# iov-board-1_2.net
KiCad netlist of a schematic drawn in EAGLE
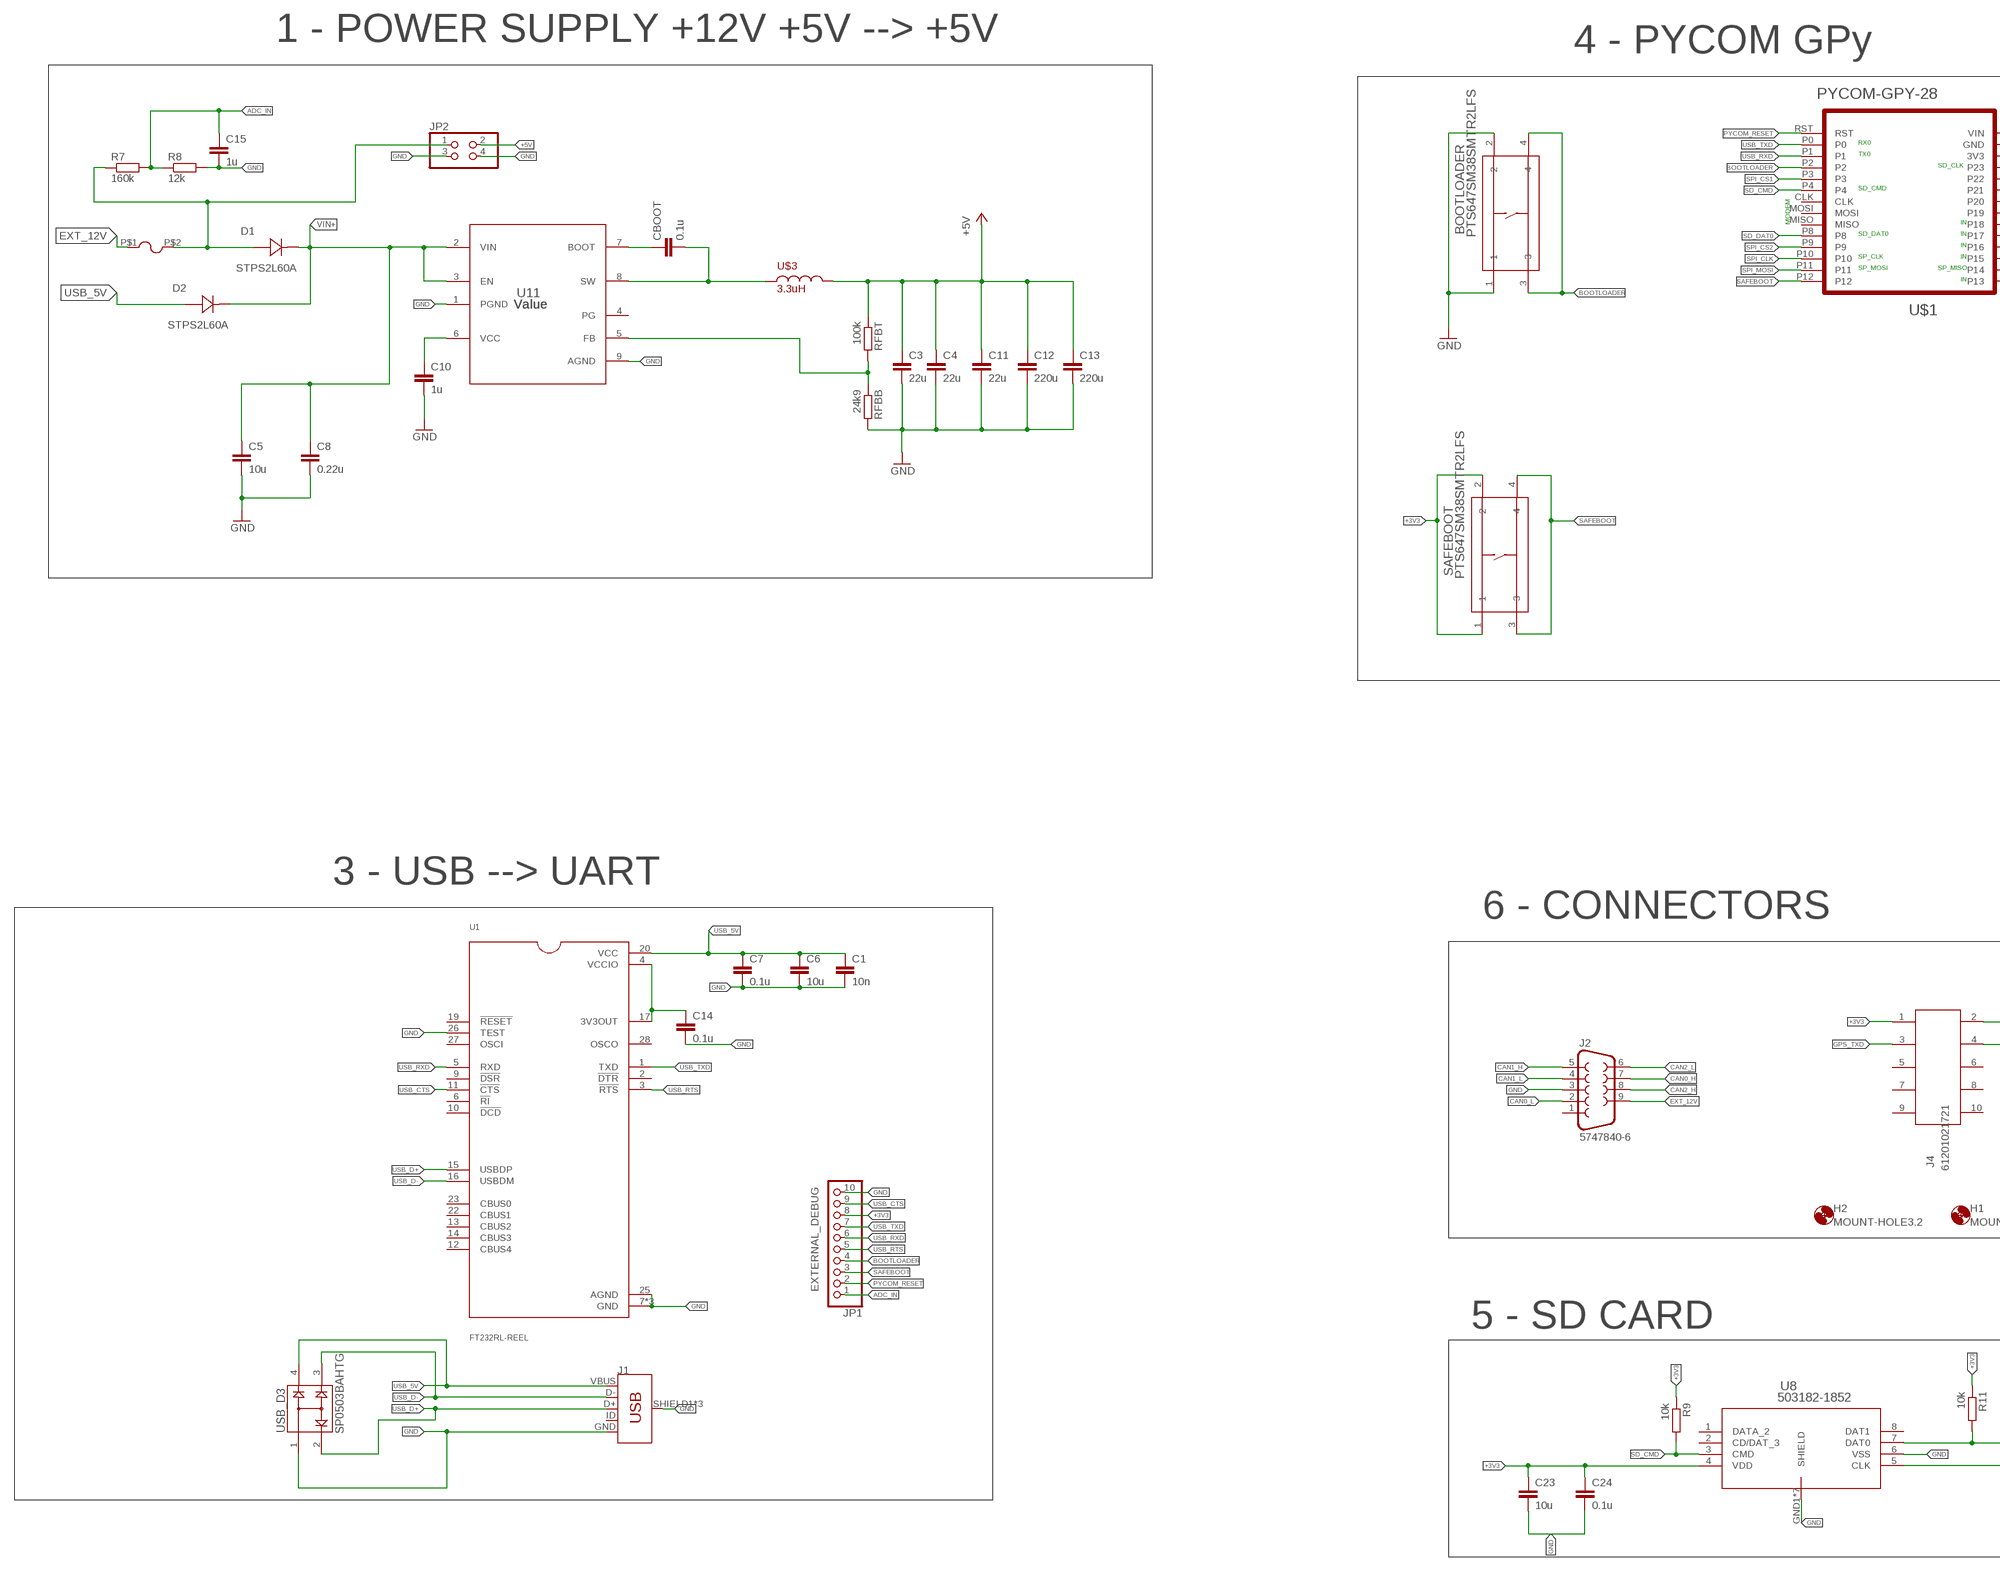
[diagram p0: schematic, sheet 1, part 1 of 2]
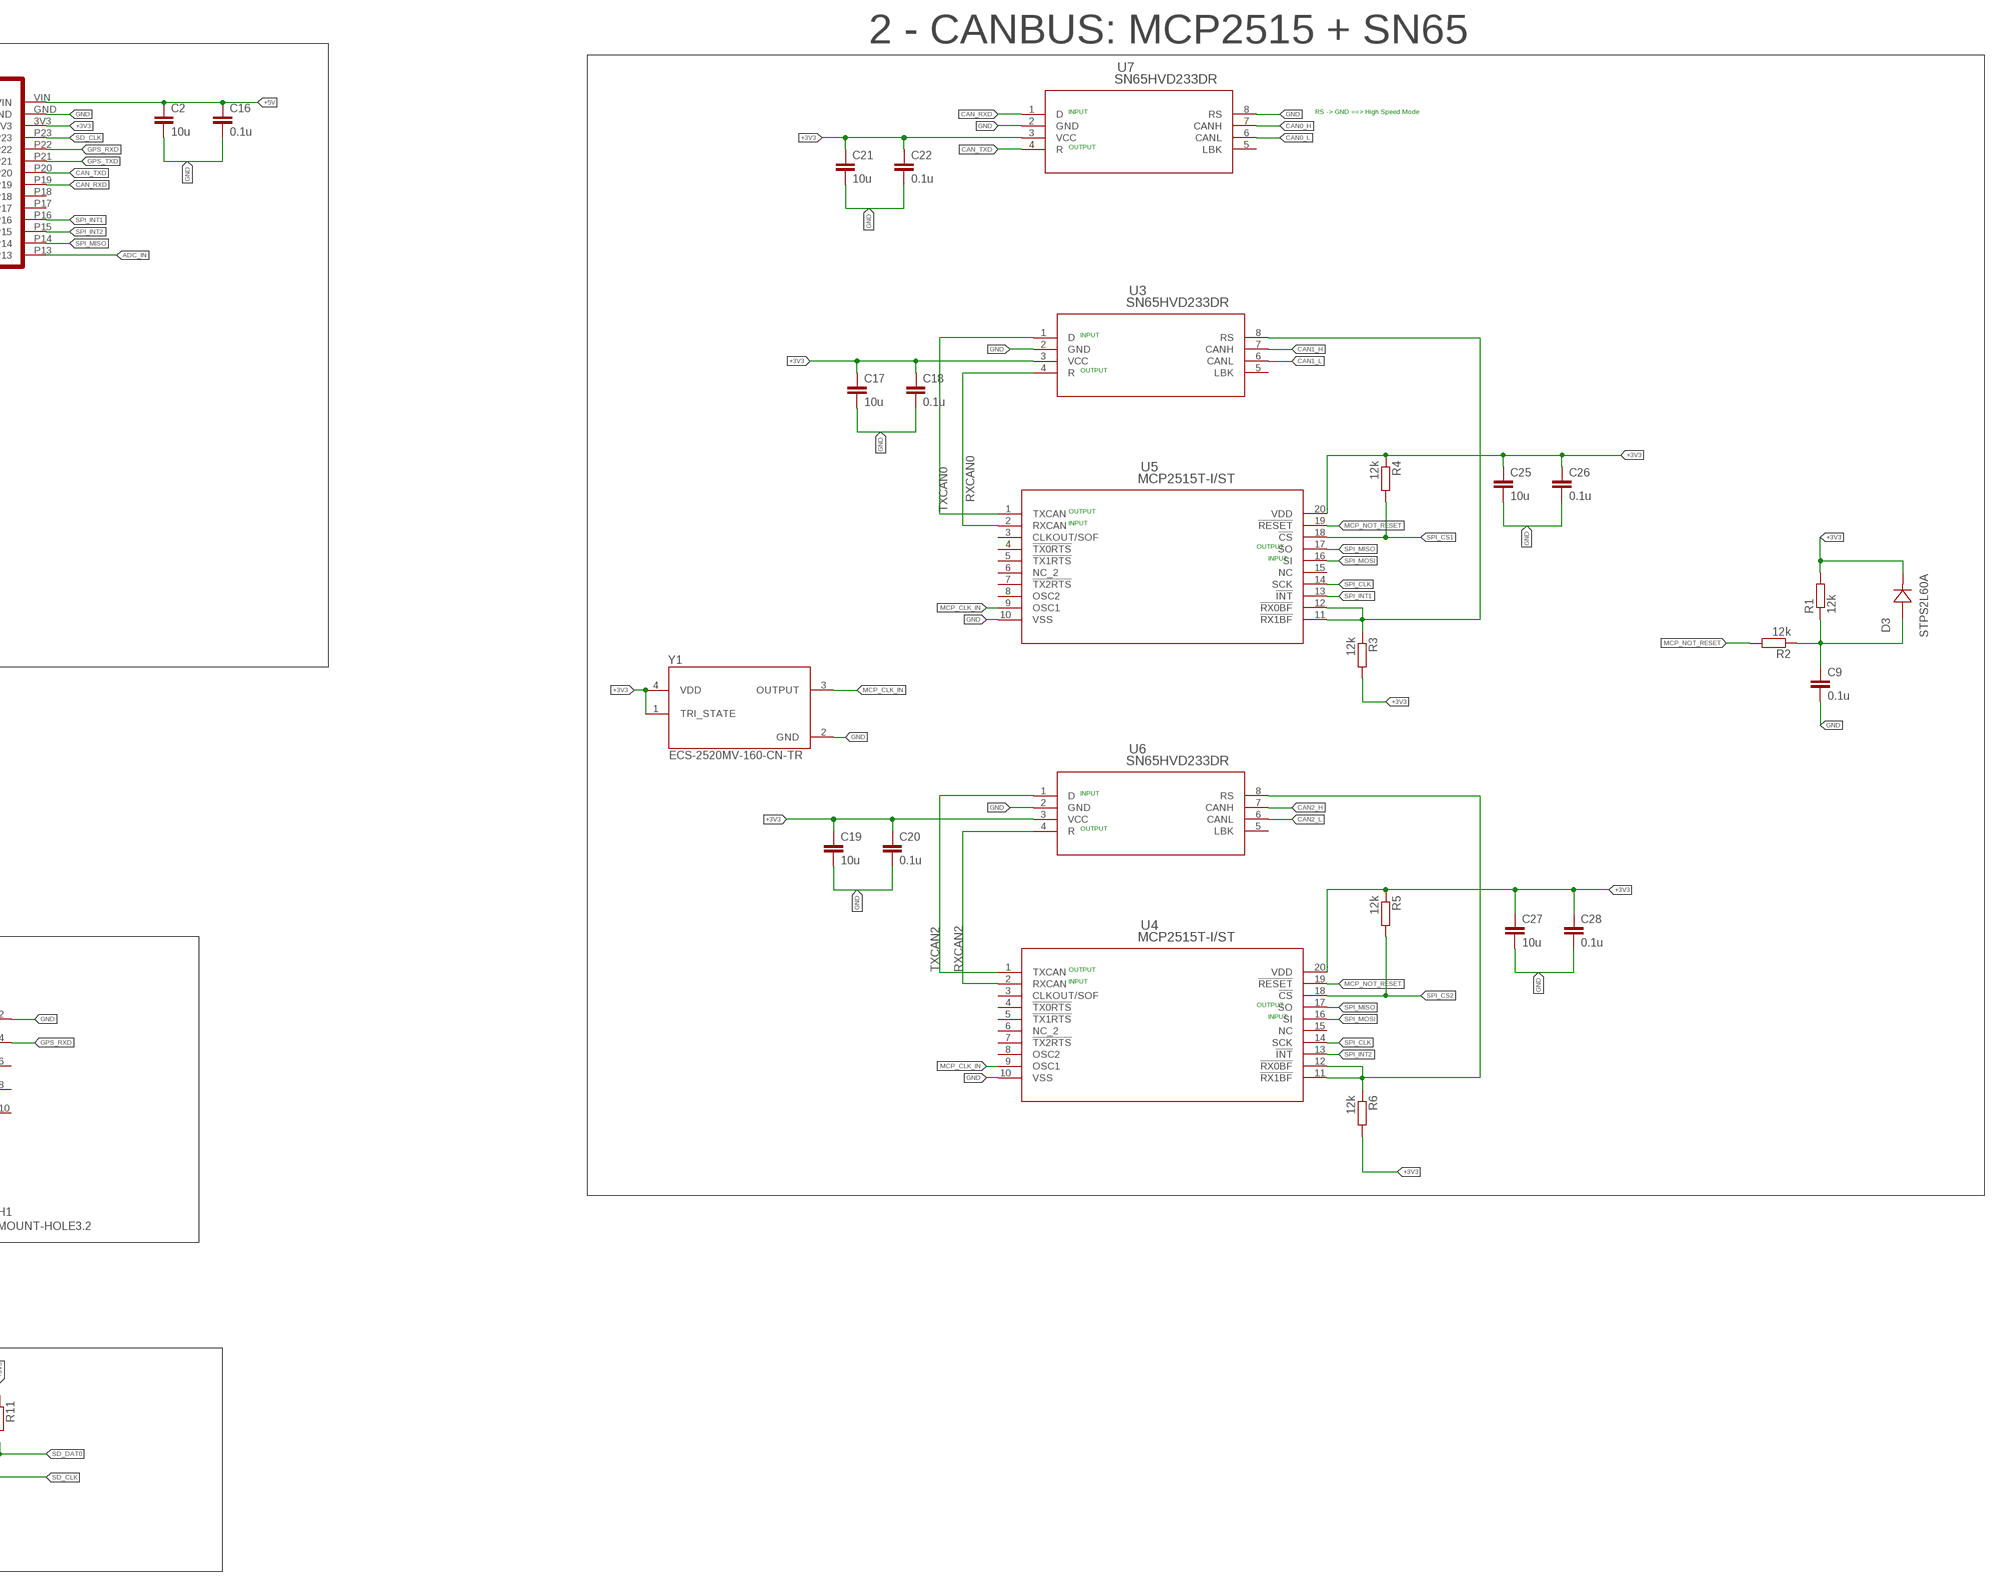
[diagram p1: schematic, sheet 1, part 2 of 2]

(export (version "E")
  (design (tool "Eeschema 10.0.6"))
  (components
    (comp (ref "BOOTLOADER")
      (value "PTS647SM38SMTR2LFS")
      (footprint "eagle-import:SW_PTS647SM38SMTR2LFS_CNK")
      (fields (field (name "COPYRIGHT") "Copyright (C) 2018 Accelerated Designs. All rights reserved"))
      (libsource (lib "eagle-import") (part "PTS647SM38SMTR2LFS"))
    )
    (comp (ref "C1")
      (value "10n")
      (footprint "eagle-import:C0805")
      (libsource (lib "eagle-import") (part "C-EUC0805"))
    )
    (comp (ref "C2")
      (value "10u")
      (footprint "eagle-import:C0805")
      (libsource (lib "eagle-import") (part "C-EUC0805"))
    )
    (comp (ref "C3")
      (value "22u")
      (footprint "eagle-import:C0805")
      (libsource (lib "eagle-import") (part "C-EUC0805"))
    )
    (comp (ref "C4")
      (value "22u")
      (footprint "eagle-import:C0805")
      (libsource (lib "eagle-import") (part "C-EUC0805"))
    )
    (comp (ref "C5")
      (value "10u")
      (footprint "eagle-import:C0805")
      (libsource (lib "eagle-import") (part "C-EUC0805"))
    )
    (comp (ref "C6")
      (value "10u")
      (footprint "eagle-import:C0805")
      (libsource (lib "eagle-import") (part "C-EUC0805"))
    )
    (comp (ref "C7")
      (value "0.1u")
      (footprint "eagle-import:C0805")
      (libsource (lib "eagle-import") (part "C-EUC0805"))
    )
    (comp (ref "C8")
      (value "0.22u")
      (footprint "eagle-import:C0805")
      (libsource (lib "eagle-import") (part "C-EUC0805"))
    )
    (comp (ref "C9")
      (value "0.1u")
      (footprint "eagle-import:C0805")
      (libsource (lib "eagle-import") (part "C-EUC0805"))
    )
    (comp (ref "C10")
      (value "1u")
      (footprint "eagle-import:C0805")
      (libsource (lib "eagle-import") (part "C-EUC0805"))
    )
    (comp (ref "C11")
      (value "22u")
      (footprint "eagle-import:C0805")
      (libsource (lib "eagle-import") (part "C-EUC0805"))
    )
    (comp (ref "C12")
      (value "220u")
      (footprint "eagle-import:C1210")
      (libsource (lib "eagle-import") (part "C-EUC1210"))
    )
    (comp (ref "C13")
      (value "220u")
      (footprint "eagle-import:C1210")
      (libsource (lib "eagle-import") (part "C-EUC1210"))
    )
    (comp (ref "C14")
      (value "0.1u")
      (footprint "eagle-import:C0805")
      (libsource (lib "eagle-import") (part "C-EUC0805"))
    )
    (comp (ref "C15")
      (value "1u")
      (footprint "eagle-import:C0805")
      (libsource (lib "eagle-import") (part "C-EUC0805"))
    )
    (comp (ref "C16")
      (value "0.1u")
      (footprint "eagle-import:C0805")
      (libsource (lib "eagle-import") (part "C-EUC0805"))
    )
    (comp (ref "C17")
      (value "10u")
      (footprint "eagle-import:C0805")
      (libsource (lib "eagle-import") (part "C-EUC0805"))
    )
    (comp (ref "C18")
      (value "0.1u")
      (footprint "eagle-import:C0805")
      (libsource (lib "eagle-import") (part "C-EUC0805"))
    )
    (comp (ref "C19")
      (value "10u")
      (footprint "eagle-import:C0805")
      (libsource (lib "eagle-import") (part "C-EUC0805"))
    )
    (comp (ref "C20")
      (value "0.1u")
      (footprint "eagle-import:C0805")
      (libsource (lib "eagle-import") (part "C-EUC0805"))
    )
    (comp (ref "C21")
      (value "10u")
      (footprint "eagle-import:C0805")
      (libsource (lib "eagle-import") (part "C-EUC0805"))
    )
    (comp (ref "C22")
      (value "0.1u")
      (footprint "eagle-import:C0805")
      (libsource (lib "eagle-import") (part "C-EUC0805"))
    )
    (comp (ref "C23")
      (value "10u")
      (footprint "eagle-import:C0805")
      (libsource (lib "eagle-import") (part "C-EUC0805"))
    )
    (comp (ref "C24")
      (value "0.1u")
      (footprint "eagle-import:C0805")
      (libsource (lib "eagle-import") (part "C-EUC0805"))
    )
    (comp (ref "C25")
      (value "10u")
      (footprint "eagle-import:C0805")
      (libsource (lib "eagle-import") (part "C-EUC0805"))
    )
    (comp (ref "C26")
      (value "0.1u")
      (footprint "eagle-import:C0805")
      (libsource (lib "eagle-import") (part "C-EUC0805"))
    )
    (comp (ref "C27")
      (value "10u")
      (footprint "eagle-import:C0805")
      (libsource (lib "eagle-import") (part "C-EUC0805"))
    )
    (comp (ref "C28")
      (value "0.1u")
      (footprint "eagle-import:C0805")
      (libsource (lib "eagle-import") (part "C-EUC0805"))
    )
    (comp (ref "CBOOT")
      (value "0.1u")
      (footprint "eagle-import:C0805")
      (libsource (lib "eagle-import") (part "C-EUC0805"))
    )
    (comp (ref "D1")
      (value "STPS2L60A")
      (footprint "eagle-import:SMA_STM")
      (libsource (lib "eagle-import") (part "STPS2L60A"))
    )
    (comp (ref "D2")
      (value "STPS2L60A")
      (footprint "eagle-import:SMA_STM")
      (libsource (lib "eagle-import") (part "STPS2L60A"))
    )
    (comp (ref "D3")
      (value "STPS2L60A")
      (footprint "eagle-import:SMA_STM")
      (libsource (lib "eagle-import") (part "STPS2L60A"))
    )
    (comp (ref "H1")
      (value "MOUNT-HOLE3.2")
      (footprint "eagle-import:3,2")
      (libsource (lib "eagle-import") (part "MOUNT-HOLE3.2"))
    )
    (comp (ref "H2")
      (value "MOUNT-HOLE3.2")
      (footprint "eagle-import:3,2")
      (libsource (lib "eagle-import") (part "MOUNT-HOLE3.2"))
    )
    (comp (ref "J1")
      (value "USB_MICRO-B_FEMALE-SMT")
      (footprint "eagle-import:USB-B-MICRO-SMD")
      (libsource (lib "eagle-import") (part "USB_MICRO-B_FEMALE-SMT"))
    )
    (comp (ref "J2")
      (value "5747840-6")
      (footprint "eagle-import:TE_5747840-6")
      (libsource (lib "eagle-import") (part "5747840-6"))
    )
    (comp (ref "J4")
      (value "61201021721")
      (footprint "eagle-import:61201021721")
      (fields (field (name "MF") "Wurth Electronics"))
      (libsource (lib "eagle-import") (part "61201021721"))
    )
    (comp (ref "JP1")
      (value "EXTERNAL_DEBUG")
      (footprint "eagle-import:1X10")
      (libsource (lib "eagle-import") (part "PINHD-1X10"))
    )
    (comp (ref "JP2")
      (value "PINHD-2X2")
      (footprint "eagle-import:2X02")
      (libsource (lib "eagle-import") (part "PINHD-2X2"))
    )
    (comp (ref "R1")
      (value "12k")
      (footprint "eagle-import:R0805")
      (libsource (lib "eagle-import") (part "R-EU_R0805"))
    )
    (comp (ref "R2")
      (value "12k")
      (footprint "eagle-import:R0805")
      (libsource (lib "eagle-import") (part "R-EU_R0805"))
    )
    (comp (ref "R3")
      (value "12k")
      (footprint "eagle-import:R0805")
      (libsource (lib "eagle-import") (part "R-EU_R0805"))
    )
    (comp (ref "R4")
      (value "12k")
      (footprint "eagle-import:R0805")
      (libsource (lib "eagle-import") (part "R-EU_R0805"))
    )
    (comp (ref "R5")
      (value "12k")
      (footprint "eagle-import:R0805")
      (libsource (lib "eagle-import") (part "R-EU_R0805"))
    )
    (comp (ref "R6")
      (value "12k")
      (footprint "eagle-import:R0805")
      (libsource (lib "eagle-import") (part "R-EU_R0805"))
    )
    (comp (ref "R7")
      (value "160k")
      (footprint "eagle-import:R0805")
      (libsource (lib "eagle-import") (part "R-EU_R0805"))
    )
    (comp (ref "R8")
      (value "12k")
      (footprint "eagle-import:R0805")
      (libsource (lib "eagle-import") (part "R-EU_R0805"))
    )
    (comp (ref "R9")
      (value "10k")
      (footprint "eagle-import:R0805")
      (libsource (lib "eagle-import") (part "R-EU_R0805"))
    )
    (comp (ref "R11")
      (value "10k")
      (footprint "eagle-import:R0805")
      (libsource (lib "eagle-import") (part "R-EU_R0805"))
    )
    (comp (ref "RFBB")
      (value "24k9")
      (footprint "eagle-import:R0805")
      (libsource (lib "eagle-import") (part "R-EU_R0805"))
    )
    (comp (ref "RFBT")
      (value "100k")
      (footprint "eagle-import:R0805")
      (libsource (lib "eagle-import") (part "R-EU_R0805"))
    )
    (comp (ref "SAFEBOOT")
      (value "PTS647SM38SMTR2LFS")
      (footprint "eagle-import:SW_PTS647SM38SMTR2LFS_CNK")
      (fields (field (name "COPYRIGHT") "Copyright (C) 2018 Accelerated Designs. All rights reserved"))
      (libsource (lib "eagle-import") (part "PTS647SM38SMTR2LFS"))
    )
    (comp (ref "U$1")
      (value "PYCOM-GPY-28")
      (footprint "eagle-import:PYCOM_GPY-28")
      (libsource (lib "eagle-import") (part "PYCOM-GPY-28"))
    )
    (comp (ref "U$3")
      (value "3.3uH")
      (footprint "eagle-import:3_3_UH")
      (libsource (lib "eagle-import") (part "3_3_UH"))
    )
    (comp (ref "U$4")
      (value "LITTLEFUSE_658")
      (footprint "eagle-import:LITTLEFUSE_658")
      (libsource (lib "eagle-import") (part "LITTLEFUSE_658"))
    )
    (comp (ref "U1")
      (value "FT232RL-REEL")
      (footprint "eagle-import:SOP65P780X200-28N")
      (fields (field (name "MF") "FTDI,"))
      (libsource (lib "eagle-import") (part "FT232RL-REEL"))
    )
    (comp (ref "U3")
      (value "SN65HVD233DR")
      (footprint "eagle-import:D8")
      (fields
        (field (name "GENERIC_PART_NUMBER") "SN65HVD233")
        (field (name "MANUFACTURER") "Texas Instruments")
      )
      (libsource (lib "eagle-import") (part "SN65HVD233DR"))
    )
    (comp (ref "U4")
      (value "MCP2515T-I/ST")
      (footprint "eagle-import:TSSOP20_MC_MCH")
      (libsource (lib "eagle-import") (part "MCP2515T-I/ST"))
    )
    (comp (ref "U5")
      (value "MCP2515T-I/ST")
      (footprint "eagle-import:TSSOP20_MC_MCH")
      (libsource (lib "eagle-import") (part "MCP2515T-I/ST"))
    )
    (comp (ref "U6")
      (value "SN65HVD233DR")
      (footprint "eagle-import:D8")
      (fields
        (field (name "GENERIC_PART_NUMBER") "SN65HVD233")
        (field (name "MANUFACTURER") "Texas Instruments")
      )
      (libsource (lib "eagle-import") (part "SN65HVD233DR"))
    )
    (comp (ref "U7")
      (value "SN65HVD233DR")
      (footprint "eagle-import:D8")
      (fields
        (field (name "GENERIC_PART_NUMBER") "SN65HVD233")
        (field (name "MANUFACTURER") "Texas Instruments")
      )
      (libsource (lib "eagle-import") (part "SN65HVD233DR"))
    )
    (comp (ref "U8")
      (value "503182-1852")
      (footprint "eagle-import:503182-1852_MOL")
      (fields (field (name "COPYRIGHT") "Copyright (C) 2018 Accelerated Designs. All rights reserved"))
      (libsource (lib "eagle-import") (part "503182-1852"))
    )
    (comp (ref "U11")
      (value "Value")
      (footprint "eagle-import:DDA0008J")
      (fields (field (name "MANUFACTURER") "Texas Instruments") (field (name "PARTNUMBER") "LMR33640DDDA"))
      (libsource (lib "eagle-import") (part "LMR33640DDDAR"))
    )
    (comp (ref "USB_D3")
      (value "SP0503BAHTG")
      (footprint "eagle-import:SOT143")
      (fields (field (name "MF") "Littelfuse Inc."))
      (libsource (lib "eagle-import") (part "SP0503BAHTG"))
    )
    (comp (ref "Y1")
      (value "ECS-2520MV-160-CN-TR")
      (footprint "eagle-import:OSC_ECS-2520S25-250-FN-TR")
      (fields (field (name "DIGI-KEY_PART_NUMBER") "XC3030CT-ND") (field (name "MF") "ECS Inc."))
      (libsource (lib "eagle-import") (part "ECS-2520MV-160-CN-TR"))
    )
  )
  (nets
    (net (code "1") (name "+3V3") (class "Default")
      (node (ref "C17") (pin "1") (pinfunction "1_1") (pintype "passive"))
      (node (ref "C18") (pin "1") (pinfunction "1_1") (pintype "passive"))
      (node (ref "C19") (pin "1") (pinfunction "1_1") (pintype "passive"))
      (node (ref "C20") (pin "1") (pinfunction "1_1") (pintype "passive"))
      (node (ref "C21") (pin "1") (pinfunction "1_1") (pintype "passive"))
      (node (ref "C22") (pin "1") (pinfunction "1_1") (pintype "passive"))
      (node (ref "C23") (pin "1") (pinfunction "1_1") (pintype "passive"))
      (node (ref "C24") (pin "1") (pinfunction "1_1") (pintype "passive"))
      (node (ref "C25") (pin "1") (pinfunction "1_1") (pintype "passive"))
      (node (ref "C26") (pin "1") (pinfunction "1_1") (pintype "passive"))
      (node (ref "C27") (pin "1") (pinfunction "1_1") (pintype "passive"))
      (node (ref "C28") (pin "1") (pinfunction "1_1") (pintype "passive"))
      (node (ref "D3") (pin "1") (pinfunction "1_1") (pintype "passive"))
      (node (ref "J4") (pin "1") (pinfunction "10_1") (pintype "passive"))
      (node (ref "JP1") (pin "8") (pinfunction "8_8") (pintype "passive"))
      (node (ref "R1") (pin "2") (pinfunction "2_2") (pintype "passive"))
      (node (ref "R11") (pin "1") (pinfunction "1_1") (pintype "passive"))
      (node (ref "R3") (pin "2") (pinfunction "2_2") (pintype "passive"))
      (node (ref "R4") (pin "1") (pinfunction "1_1") (pintype "passive"))
      (node (ref "R5") (pin "1") (pinfunction "1_1") (pintype "passive"))
      (node (ref "R6") (pin "2") (pinfunction "2_2") (pintype "passive"))
      (node (ref "R9") (pin "1") (pinfunction "1_1") (pintype "passive"))
      (node (ref "SAFEBOOT") (pin "1") (pinfunction "1_1") (pintype "passive"))
      (node (ref "SAFEBOOT") (pin "2") (pinfunction "2_2") (pintype "passive"))
      (node (ref "U$1") (pin "3V3") (pinfunction "3V3_3V3") (pintype "bidirectional"))
      (node (ref "U3") (pin "3") (pinfunction "VCC_3") (pintype "power_in"))
      (node (ref "U4") (pin "20") (pinfunction "VDD_20") (pintype "passive"))
      (node (ref "U5") (pin "20") (pinfunction "VDD_20") (pintype "passive"))
      (node (ref "U6") (pin "3") (pinfunction "VCC_3") (pintype "power_in"))
      (node (ref "U7") (pin "3") (pinfunction "VCC_3") (pintype "power_in"))
      (node (ref "U8") (pin "4") (pinfunction "VDD_4") (pintype "power_in"))
      (node (ref "Y1") (pin "1") (pinfunction "TRI_STATE_1") (pintype "input"))
      (node (ref "Y1") (pin "4") (pinfunction "VDD_4") (pintype "input"))
    )
    (net (code "2") (name "+5V") (class "Default")
      (node (ref "C11") (pin "1") (pinfunction "1_1") (pintype "passive"))
      (node (ref "C12") (pin "1") (pinfunction "1_1") (pintype "passive"))
      (node (ref "C13") (pin "1") (pinfunction "1_1") (pintype "passive"))
      (node (ref "C16") (pin "1") (pinfunction "1_1") (pintype "passive"))
      (node (ref "C2") (pin "1") (pinfunction "1_1") (pintype "passive"))
      (node (ref "C3") (pin "1") (pinfunction "1_1") (pintype "passive"))
      (node (ref "C4") (pin "1") (pinfunction "1_1") (pintype "passive"))
      (node (ref "JP2") (pin "2") (pinfunction "2_2") (pintype "passive"))
      (node (ref "RFBT") (pin "1") (pinfunction "1_1") (pintype "passive"))
      (node (ref "U$1") (pin "VIN") (pinfunction "VIN_VIN") (pintype "bidirectional"))
      (node (ref "U$3") (pin "P$2") (pinfunction "P$2_P$2") (pintype "bidirectional"))
    )
    (net (code "3") (name "/RXCAN0") (class "Default")
      (node (ref "U3") (pin "4") (pinfunction "R_4") (pintype "input"))
      (node (ref "U5") (pin "2") (pinfunction "RXCAN_2") (pintype "passive"))
    )
    (net (code "4") (name "/RXCAN2") (class "Default")
      (node (ref "U4") (pin "2") (pinfunction "RXCAN_2") (pintype "passive"))
      (node (ref "U6") (pin "4") (pinfunction "R_4") (pintype "input"))
    )
    (net (code "5") (name "/TXCAN0") (class "Default")
      (node (ref "U3") (pin "1") (pinfunction "D_1") (pintype "input"))
      (node (ref "U5") (pin "1") (pinfunction "TXCAN_1") (pintype "passive"))
    )
    (net (code "6") (name "/TXCAN2") (class "Default")
      (node (ref "U4") (pin "1") (pinfunction "TXCAN_1") (pintype "passive"))
      (node (ref "U6") (pin "1") (pinfunction "D_1") (pintype "input"))
    )
    (net (code "7") (name "ADC_IN") (class "Default")
      (node (ref "C15") (pin "1") (pinfunction "1_1") (pintype "passive"))
      (node (ref "JP1") (pin "1") (pinfunction "1_1") (pintype "passive"))
      (node (ref "R7") (pin "2") (pinfunction "2_2") (pintype "passive"))
      (node (ref "R8") (pin "1") (pinfunction "1_1") (pintype "passive"))
      (node (ref "U$1") (pin "P13") (pinfunction "P13_P13") (pintype "bidirectional"))
    )
    (net (code "8") (name "BOOTLOADER") (class "Default")
      (node (ref "BOOTLOADER") (pin "3") (pinfunction "3_3") (pintype "passive"))
      (node (ref "BOOTLOADER") (pin "4") (pinfunction "4_4") (pintype "passive"))
      (node (ref "JP1") (pin "4") (pinfunction "4_4") (pintype "passive"))
      (node (ref "U$1") (pin "P2") (pinfunction "P2_P2") (pintype "bidirectional"))
    )
    (net (code "9") (name "CAN0_H") (class "Default")
      (node (ref "J2") (pin "7") (pinfunction "7_7") (pintype "passive"))
      (node (ref "U7") (pin "7") (pinfunction "CANH_7") (pintype "output"))
    )
    (net (code "10") (name "CAN0_L") (class "Default")
      (node (ref "J2") (pin "2") (pinfunction "2_2") (pintype "passive"))
      (node (ref "U7") (pin "6") (pinfunction "CANL_6") (pintype "output"))
    )
    (net (code "11") (name "CAN1_H") (class "Default")
      (node (ref "J2") (pin "5") (pinfunction "5_5") (pintype "passive"))
      (node (ref "U3") (pin "7") (pinfunction "CANH_7") (pintype "output"))
    )
    (net (code "12") (name "CAN1_L") (class "Default")
      (node (ref "J2") (pin "4") (pinfunction "4_4") (pintype "passive"))
      (node (ref "U3") (pin "6") (pinfunction "CANL_6") (pintype "output"))
    )
    (net (code "13") (name "CAN2_H") (class "Default")
      (node (ref "J2") (pin "8") (pinfunction "8_8") (pintype "passive"))
      (node (ref "U6") (pin "7") (pinfunction "CANH_7") (pintype "output"))
    )
    (net (code "14") (name "CAN2_L") (class "Default")
      (node (ref "J2") (pin "6") (pinfunction "6_6") (pintype "passive"))
      (node (ref "U6") (pin "6") (pinfunction "CANL_6") (pintype "output"))
    )
    (net (code "15") (name "CAN_RXD") (class "Default")
      (node (ref "U$1") (pin "P19") (pinfunction "P19_P19") (pintype "bidirectional"))
      (node (ref "U7") (pin "1") (pinfunction "D_1") (pintype "input"))
    )
    (net (code "16") (name "CAN_TXD") (class "Default")
      (node (ref "U$1") (pin "P20") (pinfunction "P20_P20") (pintype "bidirectional"))
      (node (ref "U7") (pin "4") (pinfunction "R_4") (pintype "input"))
    )
    (net (code "17") (name "EXT_12V") (class "Default")
      (node (ref "J2") (pin "9") (pinfunction "9_9") (pintype "passive"))
      (node (ref "U$4") (pin "P$1") (pinfunction "P$1_P$1") (pintype "bidirectional"))
    )
    (net (code "18") (name "GND") (class "Default")
      (node (ref "BOOTLOADER") (pin "1") (pinfunction "1_1") (pintype "passive"))
      (node (ref "BOOTLOADER") (pin "2") (pinfunction "2_2") (pintype "passive"))
      (node (ref "C1") (pin "2") (pinfunction "2_2") (pintype "passive"))
      (node (ref "C10") (pin "2") (pinfunction "2_2") (pintype "passive"))
      (node (ref "C11") (pin "2") (pinfunction "2_2") (pintype "passive"))
      (node (ref "C12") (pin "2") (pinfunction "2_2") (pintype "passive"))
      (node (ref "C13") (pin "2") (pinfunction "2_2") (pintype "passive"))
      (node (ref "C14") (pin "2") (pinfunction "2_2") (pintype "passive"))
      (node (ref "C15") (pin "2") (pinfunction "2_2") (pintype "passive"))
      (node (ref "C16") (pin "2") (pinfunction "2_2") (pintype "passive"))
      (node (ref "C17") (pin "2") (pinfunction "2_2") (pintype "passive"))
      (node (ref "C18") (pin "2") (pinfunction "2_2") (pintype "passive"))
      (node (ref "C19") (pin "2") (pinfunction "2_2") (pintype "passive"))
      (node (ref "C2") (pin "2") (pinfunction "2_2") (pintype "passive"))
      (node (ref "C20") (pin "2") (pinfunction "2_2") (pintype "passive"))
      (node (ref "C21") (pin "2") (pinfunction "2_2") (pintype "passive"))
      (node (ref "C22") (pin "2") (pinfunction "2_2") (pintype "passive"))
      (node (ref "C23") (pin "2") (pinfunction "2_2") (pintype "passive"))
      (node (ref "C24") (pin "2") (pinfunction "2_2") (pintype "passive"))
      (node (ref "C25") (pin "2") (pinfunction "2_2") (pintype "passive"))
      (node (ref "C26") (pin "2") (pinfunction "2_2") (pintype "passive"))
      (node (ref "C27") (pin "2") (pinfunction "2_2") (pintype "passive"))
      (node (ref "C28") (pin "2") (pinfunction "2_2") (pintype "passive"))
      (node (ref "C3") (pin "2") (pinfunction "2_2") (pintype "passive"))
      (node (ref "C4") (pin "2") (pinfunction "2_2") (pintype "passive"))
      (node (ref "C5") (pin "2") (pinfunction "2_2") (pintype "passive"))
      (node (ref "C6") (pin "2") (pinfunction "2_2") (pintype "passive"))
      (node (ref "C7") (pin "2") (pinfunction "2_2") (pintype "passive"))
      (node (ref "C8") (pin "2") (pinfunction "2_2") (pintype "passive"))
      (node (ref "C9") (pin "2") (pinfunction "2_2") (pintype "passive"))
      (node (ref "J1") (pin "GND") (pinfunction "GND_GND") (pintype "power_in"))
      (node (ref "J1") (pin "SHIELD1") (pinfunction "SHIELD_SHIELD1") (pintype "bidirectional"))
      (node (ref "J1") (pin "SHIELD2") (pinfunction "SHIELD_SHIELD2") (pintype "bidirectional"))
      (node (ref "J1") (pin "SHIELD3") (pinfunction "SHIELD_SHIELD3") (pintype "bidirectional"))
      (node (ref "J2") (pin "3") (pinfunction "3_3") (pintype "passive"))
      (node (ref "J4") (pin "2") (pinfunction "9_2") (pintype "passive"))
      (node (ref "JP1") (pin "10") (pinfunction "10_10") (pintype "passive"))
      (node (ref "JP2") (pin "3") (pinfunction "3_3") (pintype "passive"))
      (node (ref "JP2") (pin "4") (pinfunction "4_4") (pintype "passive"))
      (node (ref "R8") (pin "2") (pinfunction "2_2") (pintype "passive"))
      (node (ref "RFBB") (pin "2") (pinfunction "2_2") (pintype "passive"))
      (node (ref "U$1") (pin "GND") (pinfunction "GND_GND") (pintype "bidirectional"))
      (node (ref "U1") (pin "18") (pinfunction "GND_18") (pintype "passive"))
      (node (ref "U1") (pin "21") (pinfunction "GND_21") (pintype "passive"))
      (node (ref "U1") (pin "25") (pinfunction "AGND_25") (pintype "passive"))
      (node (ref "U1") (pin "26") (pinfunction "TEST_26") (pintype "input"))
      (node (ref "U1") (pin "7") (pinfunction "GND_7") (pintype "passive"))
      (node (ref "U11") (pin "1") (pinfunction "PGND_1") (pintype "power_in"))
      (node (ref "U11") (pin "9") (pinfunction "AGND_9") (pintype "passive"))
      (node (ref "U3") (pin "2") (pinfunction "GND_2") (pintype "power_in"))
      (node (ref "U4") (pin "10") (pinfunction "VSS_10") (pintype "passive"))
      (node (ref "U5") (pin "10") (pinfunction "VSS_10") (pintype "passive"))
      (node (ref "U6") (pin "2") (pinfunction "GND_2") (pintype "power_in"))
      (node (ref "U7") (pin "2") (pinfunction "GND_2") (pintype "power_in"))
      (node (ref "U7") (pin "8") (pinfunction "RS_8") (pintype "input"))
      (node (ref "U8") (pin "6") (pinfunction "VSS_6") (pintype "passive"))
      (node (ref "U8") (pin "GND1") (pinfunction "SHIELD_GND1") (pintype "bidirectional"))
      (node (ref "U8") (pin "GND2") (pinfunction "SHIELD_GND2") (pintype "bidirectional"))
      (node (ref "U8") (pin "GND3") (pinfunction "SHIELD_GND3") (pintype "bidirectional"))
      (node (ref "U8") (pin "GND4") (pinfunction "SHIELD_GND4") (pintype "bidirectional"))
      (node (ref "U8") (pin "GND5") (pinfunction "SHIELD_GND5") (pintype "bidirectional"))
      (node (ref "U8") (pin "GND6") (pinfunction "SHIELD_GND6") (pintype "bidirectional"))
      (node (ref "U8") (pin "GND7") (pinfunction "SHIELD_GND7") (pintype "bidirectional"))
      (node (ref "USB_D3") (pin "1") (pinfunction "1_1") (pintype "passive"))
      (node (ref "Y1") (pin "2") (pinfunction "GND_2") (pintype "power_in"))
    )
    (net (code "19") (name "GPS_RXD") (class "Default")
      (node (ref "J4") (pin "4") (pinfunction "7_4") (pintype "passive"))
      (node (ref "U$1") (pin "P22") (pinfunction "P22_P22") (pintype "bidirectional"))
    )
    (net (code "20") (name "GPS_TXD") (class "Default")
      (node (ref "J4") (pin "3") (pinfunction "8_3") (pintype "passive"))
      (node (ref "U$1") (pin "P21") (pinfunction "P21_P21") (pintype "bidirectional"))
    )
    (net (code "21") (name "MCP_CLK_IN") (class "Default")
      (node (ref "U4") (pin "9") (pinfunction "OSC1_9") (pintype "passive"))
      (node (ref "U5") (pin "9") (pinfunction "OSC1_9") (pintype "passive"))
      (node (ref "Y1") (pin "3") (pinfunction "OUTPUT_3") (pintype "output"))
    )
    (net (code "22") (name "MCP_NOT_RESET") (class "Default")
      (node (ref "R2") (pin "2") (pinfunction "2_2") (pintype "passive"))
      (node (ref "U4") (pin "19") (pinfunction "~{RESET}_19") (pintype "passive"))
      (node (ref "U5") (pin "19") (pinfunction "~{RESET}_19") (pintype "passive"))
    )
    (net (code "23") (name "Net-(C9-Pad1)") (class "Default")
      (node (ref "C9") (pin "1") (pinfunction "1_1") (pintype "passive"))
      (node (ref "D3") (pin "2") (pinfunction "2_2") (pintype "passive"))
      (node (ref "R1") (pin "1") (pinfunction "1_1") (pintype "passive"))
      (node (ref "R2") (pin "1") (pinfunction "1_1") (pintype "passive"))
    )
    (net (code "24") (name "Net-(D1-Pad2)") (class "Default")
      (node (ref "D1") (pin "2") (pinfunction "2_2") (pintype "passive"))
      (node (ref "JP2") (pin "1") (pinfunction "1_1") (pintype "passive"))
      (node (ref "R7") (pin "1") (pinfunction "1_1") (pintype "passive"))
      (node (ref "U$4") (pin "P$2") (pinfunction "P$2_P$2") (pintype "bidirectional"))
    )
    (net (code "25") (name "Net-(U1-3V3OUT)") (class "Default")
      (node (ref "C14") (pin "1") (pinfunction "1_1") (pintype "passive"))
      (node (ref "U1") (pin "17") (pinfunction "3V3OUT_17") (pintype "output"))
      (node (ref "U1") (pin "4") (pinfunction "VCCIO_4") (pintype "power_in"))
    )
    (net (code "26") (name "Net-(U3-RS)") (class "Default")
      (node (ref "R3") (pin "1") (pinfunction "1_1") (pintype "passive"))
      (node (ref "U3") (pin "8") (pinfunction "RS_8") (pintype "input"))
      (node (ref "U5") (pin "11") (pinfunction "~{RX1BF}_11") (pintype "passive"))
      (node (ref "U5") (pin "12") (pinfunction "~{RX0BF}_12") (pintype "passive"))
    )
    (net (code "27") (name "Net-(U4-~{RX0BF})") (class "Default")
      (node (ref "R6") (pin "1") (pinfunction "1_1") (pintype "passive"))
      (node (ref "U4") (pin "11") (pinfunction "~{RX1BF}_11") (pintype "passive"))
      (node (ref "U4") (pin "12") (pinfunction "~{RX0BF}_12") (pintype "passive"))
      (node (ref "U6") (pin "8") (pinfunction "RS_8") (pintype "input"))
    )
    (net (code "28") (name "Net-(U11-BOOT)") (class "Default")
      (node (ref "CBOOT") (pin "1") (pinfunction "1_1") (pintype "passive"))
      (node (ref "U11") (pin "7") (pinfunction "BOOT_7") (pintype "power_in"))
    )
    (net (code "29") (name "Net-(U11-FB)") (class "Default")
      (node (ref "RFBB") (pin "1") (pinfunction "1_1") (pintype "passive"))
      (node (ref "RFBT") (pin "2") (pinfunction "2_2") (pintype "passive"))
      (node (ref "U11") (pin "5") (pinfunction "FB_5") (pintype "input"))
    )
    (net (code "30") (name "Net-(U11-SW)") (class "Default")
      (node (ref "CBOOT") (pin "2") (pinfunction "2_2") (pintype "passive"))
      (node (ref "U$3") (pin "P$1") (pinfunction "P$1_P$1") (pintype "bidirectional"))
      (node (ref "U11") (pin "8") (pinfunction "SW_8") (pintype "power_in"))
    )
    (net (code "31") (name "Net-(U11-VCC)") (class "Default")
      (node (ref "C10") (pin "1") (pinfunction "1_1") (pintype "passive"))
      (node (ref "U11") (pin "6") (pinfunction "VCC_6") (pintype "power_in"))
    )
    (net (code "32") (name "PYCOM_RESET") (class "Default")
      (node (ref "JP1") (pin "2") (pinfunction "2_2") (pintype "passive"))
      (node (ref "U$1") (pin "RST") (pinfunction "RST_RST") (pintype "bidirectional"))
    )
    (net (code "33") (name "SAFEBOOT") (class "Default")
      (node (ref "JP1") (pin "3") (pinfunction "3_3") (pintype "passive"))
      (node (ref "SAFEBOOT") (pin "3") (pinfunction "3_3") (pintype "passive"))
      (node (ref "SAFEBOOT") (pin "4") (pinfunction "4_4") (pintype "passive"))
      (node (ref "U$1") (pin "P12") (pinfunction "P12_P12") (pintype "bidirectional"))
    )
    (net (code "34") (name "SD_CLK") (class "Default")
      (node (ref "U$1") (pin "P23") (pinfunction "P23_P23") (pintype "bidirectional"))
      (node (ref "U8") (pin "5") (pinfunction "CLK_5") (pintype "passive"))
    )
    (net (code "35") (name "SD_CMD") (class "Default")
      (node (ref "R9") (pin "2") (pinfunction "2_2") (pintype "passive"))
      (node (ref "U$1") (pin "P4") (pinfunction "P4_P4") (pintype "bidirectional"))
      (node (ref "U8") (pin "3") (pinfunction "CMD_3") (pintype "passive"))
    )
    (net (code "36") (name "SD_DAT0") (class "Default")
      (node (ref "R11") (pin "2") (pinfunction "2_2") (pintype "passive"))
      (node (ref "U$1") (pin "P8") (pinfunction "P8_P8") (pintype "bidirectional"))
      (node (ref "U8") (pin "7") (pinfunction "DAT0_7") (pintype "bidirectional"))
    )
    (net (code "37") (name "SPI_CLK") (class "Default")
      (node (ref "U$1") (pin "P10") (pinfunction "P10_P10") (pintype "bidirectional"))
      (node (ref "U4") (pin "14") (pinfunction "SCK_14") (pintype "passive"))
      (node (ref "U5") (pin "14") (pinfunction "SCK_14") (pintype "passive"))
    )
    (net (code "38") (name "SPI_CS1") (class "Default")
      (node (ref "R4") (pin "2") (pinfunction "2_2") (pintype "passive"))
      (node (ref "U$1") (pin "P3") (pinfunction "P3_P3") (pintype "bidirectional"))
      (node (ref "U5") (pin "18") (pinfunction "~{CS}_18") (pintype "passive"))
    )
    (net (code "39") (name "SPI_CS2") (class "Default")
      (node (ref "R5") (pin "2") (pinfunction "2_2") (pintype "passive"))
      (node (ref "U$1") (pin "P9") (pinfunction "P9_P9") (pintype "bidirectional"))
      (node (ref "U4") (pin "18") (pinfunction "~{CS}_18") (pintype "passive"))
    )
    (net (code "40") (name "SPI_INT1") (class "Default")
      (node (ref "U$1") (pin "P16") (pinfunction "P16_P16") (pintype "bidirectional"))
      (node (ref "U5") (pin "13") (pinfunction "~{INT}_13") (pintype "passive"))
    )
    (net (code "41") (name "SPI_INT2") (class "Default")
      (node (ref "U$1") (pin "P15") (pinfunction "P15_P15") (pintype "bidirectional"))
      (node (ref "U4") (pin "13") (pinfunction "~{INT}_13") (pintype "passive"))
    )
    (net (code "42") (name "SPI_MISO") (class "Default")
      (node (ref "U$1") (pin "P14") (pinfunction "P14_P14") (pintype "bidirectional"))
      (node (ref "U4") (pin "17") (pinfunction "SO_17") (pintype "passive"))
      (node (ref "U5") (pin "17") (pinfunction "SO_17") (pintype "passive"))
    )
    (net (code "43") (name "SPI_MOSI") (class "Default")
      (node (ref "U$1") (pin "P11") (pinfunction "P11_P11") (pintype "bidirectional"))
      (node (ref "U4") (pin "16") (pinfunction "SI_16") (pintype "passive"))
      (node (ref "U5") (pin "16") (pinfunction "SI_16") (pintype "passive"))
    )
    (net (code "44") (name "USB_5V") (class "Default")
      (node (ref "C1") (pin "1") (pinfunction "1_1") (pintype "passive"))
      (node (ref "C6") (pin "1") (pinfunction "1_1") (pintype "passive"))
      (node (ref "C7") (pin "1") (pinfunction "1_1") (pintype "passive"))
      (node (ref "D2") (pin "2") (pinfunction "2_2") (pintype "passive"))
      (node (ref "J1") (pin "VBUS") (pinfunction "VBUS_VBUS") (pintype "power_in"))
      (node (ref "U1") (pin "20") (pinfunction "VCC_20") (pintype "power_in"))
      (node (ref "USB_D3") (pin "4") (pinfunction "4_4") (pintype "passive"))
    )
    (net (code "45") (name "USB_CTS") (class "Default")
      (node (ref "JP1") (pin "9") (pinfunction "9_9") (pintype "passive"))
      (node (ref "U1") (pin "11") (pinfunction "~{CTS}_11") (pintype "input"))
    )
    (net (code "46") (name "USB_D+") (class "Default")
      (node (ref "J1") (pin "D+") (pinfunction "D+_D+") (pintype "bidirectional"))
      (node (ref "U1") (pin "15") (pinfunction "USBDP_15") (pintype "bidirectional"))
      (node (ref "USB_D3") (pin "2") (pinfunction "2_2") (pintype "passive"))
    )
    (net (code "47") (name "USB_D-") (class "Default")
      (node (ref "J1") (pin "D-") (pinfunction "D-_D-") (pintype "bidirectional"))
      (node (ref "U1") (pin "16") (pinfunction "USBDM_16") (pintype "bidirectional"))
      (node (ref "USB_D3") (pin "3") (pinfunction "3_3") (pintype "passive"))
    )
    (net (code "48") (name "USB_RTS") (class "Default")
      (node (ref "JP1") (pin "5") (pinfunction "5_5") (pintype "passive"))
      (node (ref "U1") (pin "3") (pinfunction "~{RTS}_3") (pintype "output"))
    )
    (net (code "49") (name "USB_RXD") (class "Default")
      (node (ref "JP1") (pin "6") (pinfunction "6_6") (pintype "passive"))
      (node (ref "U$1") (pin "P1") (pinfunction "P1_P1") (pintype "bidirectional"))
      (node (ref "U1") (pin "5") (pinfunction "RXD_5") (pintype "input"))
    )
    (net (code "50") (name "USB_TXD") (class "Default")
      (node (ref "JP1") (pin "7") (pinfunction "7_7") (pintype "passive"))
      (node (ref "U$1") (pin "P0") (pinfunction "P0_P0") (pintype "bidirectional"))
      (node (ref "U1") (pin "1") (pinfunction "TXD_1") (pintype "output"))
    )
    (net (code "51") (name "VIN+") (class "Default")
      (node (ref "C5") (pin "1") (pinfunction "1_1") (pintype "passive"))
      (node (ref "C8") (pin "1") (pinfunction "1_1") (pintype "passive"))
      (node (ref "D1") (pin "1") (pinfunction "1_1") (pintype "passive"))
      (node (ref "D2") (pin "1") (pinfunction "1_1") (pintype "passive"))
      (node (ref "U11") (pin "2") (pinfunction "VIN_2") (pintype "power_in"))
      (node (ref "U11") (pin "3") (pinfunction "EN_3") (pintype "input"))
    )
    (net (code "52") (name "unconnected-(J1-PadID)") (class "Default")
      (node (ref "J1") (pin "ID") (pinfunction "ID_ID") (pintype "bidirectional"))
    )
    (net (code "53") (name "unconnected-(J2-Pad1)") (class "Default")
      (node (ref "J2") (pin "1") (pinfunction "1_1") (pintype "passive"))
    )
    (net (code "54") (name "unconnected-(J4-1-Pad10)") (class "Default")
      (node (ref "J4") (pin "10") (pinfunction "1_10") (pintype "passive"))
    )
    (net (code "55") (name "unconnected-(J4-2-Pad9)") (class "Default")
      (node (ref "J4") (pin "9") (pinfunction "2_9") (pintype "passive"))
    )
    (net (code "56") (name "unconnected-(J4-3-Pad8)") (class "Default")
      (node (ref "J4") (pin "8") (pinfunction "3_8") (pintype "passive"))
    )
    (net (code "57") (name "unconnected-(J4-4-Pad7)") (class "Default")
      (node (ref "J4") (pin "7") (pinfunction "4_7") (pintype "passive"))
    )
    (net (code "58") (name "unconnected-(J4-5-Pad6)") (class "Default")
      (node (ref "J4") (pin "6") (pinfunction "5_6") (pintype "passive"))
    )
    (net (code "59") (name "unconnected-(J4-6-Pad5)") (class "Default")
      (node (ref "J4") (pin "5") (pinfunction "6_5") (pintype "passive"))
    )
    (net (code "60") (name "unconnected-(U$1-PadCLK)") (class "Default")
      (node (ref "U$1") (pin "CLK") (pinfunction "CLK_CLK") (pintype "bidirectional"))
    )
    (net (code "61") (name "unconnected-(U$1-PadMISO)") (class "Default")
      (node (ref "U$1") (pin "MISO") (pinfunction "MISO_MISO") (pintype "bidirectional"))
    )
    (net (code "62") (name "unconnected-(U$1-PadMOSI)") (class "Default")
      (node (ref "U$1") (pin "MOSI") (pinfunction "MOSI_MOSI") (pintype "bidirectional"))
    )
    (net (code "63") (name "unconnected-(U$1-PadP17)") (class "Default")
      (node (ref "U$1") (pin "P17") (pinfunction "P17_P17") (pintype "bidirectional"))
    )
    (net (code "64") (name "unconnected-(U$1-PadP18)") (class "Default")
      (node (ref "U$1") (pin "P18") (pinfunction "P18_P18") (pintype "bidirectional"))
    )
    (net (code "65") (name "unconnected-(U1-CBUS0-Pad23)") (class "Default")
      (node (ref "U1") (pin "23") (pinfunction "CBUS0_23") (pintype "bidirectional"))
    )
    (net (code "66") (name "unconnected-(U1-CBUS1-Pad22)") (class "Default")
      (node (ref "U1") (pin "22") (pinfunction "CBUS1_22") (pintype "bidirectional"))
    )
    (net (code "67") (name "unconnected-(U1-CBUS2-Pad13)") (class "Default")
      (node (ref "U1") (pin "13") (pinfunction "CBUS2_13") (pintype "bidirectional"))
    )
    (net (code "68") (name "unconnected-(U1-CBUS3-Pad14)") (class "Default")
      (node (ref "U1") (pin "14") (pinfunction "CBUS3_14") (pintype "bidirectional"))
    )
    (net (code "69") (name "unconnected-(U1-CBUS4-Pad12)") (class "Default")
      (node (ref "U1") (pin "12") (pinfunction "CBUS4_12") (pintype "bidirectional"))
    )
    (net (code "70") (name "unconnected-(U1-OSCI-Pad27)") (class "Default")
      (node (ref "U1") (pin "27") (pinfunction "OSCI_27") (pintype "input"))
    )
    (net (code "71") (name "unconnected-(U1-OSCO-Pad28)") (class "Default")
      (node (ref "U1") (pin "28") (pinfunction "OSCO_28") (pintype "output"))
    )
    (net (code "72") (name "unconnected-(U1-~{DCD}-Pad10)") (class "Default")
      (node (ref "U1") (pin "10") (pinfunction "~{DCD}_10") (pintype "input"))
    )
    (net (code "73") (name "unconnected-(U1-~{DSR}-Pad9)") (class "Default")
      (node (ref "U1") (pin "9") (pinfunction "~{DSR}_9") (pintype "input"))
    )
    (net (code "74") (name "unconnected-(U1-~{DTR}-Pad2)") (class "Default")
      (node (ref "U1") (pin "2") (pinfunction "~{DTR}_2") (pintype "output"))
    )
    (net (code "75") (name "unconnected-(U1-~{RESET}-Pad19)") (class "Default")
      (node (ref "U1") (pin "19") (pinfunction "~{RESET}_19") (pintype "input"))
    )
    (net (code "76") (name "unconnected-(U1-~{RI}-Pad6)") (class "Default")
      (node (ref "U1") (pin "6") (pinfunction "~{RI}_6") (pintype "input"))
    )
    (net (code "77") (name "unconnected-(U3-LBK-Pad5)") (class "Default")
      (node (ref "U3") (pin "5") (pinfunction "LBK_5") (pintype "passive"))
    )
    (net (code "78") (name "unconnected-(U4-CLKOUT{slash}SOF-Pad3)") (class "Default")
      (node (ref "U4") (pin "3") (pinfunction "CLKOUT/SOF_3") (pintype "passive"))
    )
    (net (code "79") (name "unconnected-(U4-NC-Pad15)") (class "Default")
      (node (ref "U4") (pin "15") (pinfunction "NC_15") (pintype "passive"))
    )
    (net (code "80") (name "unconnected-(U4-NC_2-Pad6)") (class "Default")
      (node (ref "U4") (pin "6") (pinfunction "NC_2_6") (pintype "passive"))
    )
    (net (code "81") (name "unconnected-(U4-OSC2-Pad8)") (class "Default")
      (node (ref "U4") (pin "8") (pinfunction "OSC2_8") (pintype "passive"))
    )
    (net (code "82") (name "unconnected-(U4-~{TX0RTS}-Pad4)") (class "Default")
      (node (ref "U4") (pin "4") (pinfunction "~{TX0RTS}_4") (pintype "passive"))
    )
    (net (code "83") (name "unconnected-(U4-~{TX1RTS}-Pad5)") (class "Default")
      (node (ref "U4") (pin "5") (pinfunction "~{TX1RTS}_5") (pintype "passive"))
    )
    (net (code "84") (name "unconnected-(U4-~{TX2RTS}-Pad7)") (class "Default")
      (node (ref "U4") (pin "7") (pinfunction "~{TX2RTS}_7") (pintype "passive"))
    )
    (net (code "85") (name "unconnected-(U5-CLKOUT{slash}SOF-Pad3)") (class "Default")
      (node (ref "U5") (pin "3") (pinfunction "CLKOUT/SOF_3") (pintype "passive"))
    )
    (net (code "86") (name "unconnected-(U5-NC-Pad15)") (class "Default")
      (node (ref "U5") (pin "15") (pinfunction "NC_15") (pintype "passive"))
    )
    (net (code "87") (name "unconnected-(U5-NC_2-Pad6)") (class "Default")
      (node (ref "U5") (pin "6") (pinfunction "NC_2_6") (pintype "passive"))
    )
    (net (code "88") (name "unconnected-(U5-OSC2-Pad8)") (class "Default")
      (node (ref "U5") (pin "8") (pinfunction "OSC2_8") (pintype "passive"))
    )
    (net (code "89") (name "unconnected-(U5-~{TX0RTS}-Pad4)") (class "Default")
      (node (ref "U5") (pin "4") (pinfunction "~{TX0RTS}_4") (pintype "passive"))
    )
    (net (code "90") (name "unconnected-(U5-~{TX1RTS}-Pad5)") (class "Default")
      (node (ref "U5") (pin "5") (pinfunction "~{TX1RTS}_5") (pintype "passive"))
    )
    (net (code "91") (name "unconnected-(U5-~{TX2RTS}-Pad7)") (class "Default")
      (node (ref "U5") (pin "7") (pinfunction "~{TX2RTS}_7") (pintype "passive"))
    )
    (net (code "92") (name "unconnected-(U6-LBK-Pad5)") (class "Default")
      (node (ref "U6") (pin "5") (pinfunction "LBK_5") (pintype "passive"))
    )
    (net (code "93") (name "unconnected-(U7-LBK-Pad5)") (class "Default")
      (node (ref "U7") (pin "5") (pinfunction "LBK_5") (pintype "passive"))
    )
    (net (code "94") (name "unconnected-(U8-CD{slash}DAT_3-Pad2)") (class "Default")
      (node (ref "U8") (pin "2") (pinfunction "CD/DAT_3_2") (pintype "bidirectional"))
    )
    (net (code "95") (name "unconnected-(U8-DAT1-Pad8)") (class "Default")
      (node (ref "U8") (pin "8") (pinfunction "DAT1_8") (pintype "bidirectional"))
    )
    (net (code "96") (name "unconnected-(U8-DATA_2-Pad1)") (class "Default")
      (node (ref "U8") (pin "1") (pinfunction "DATA_2_1") (pintype "bidirectional"))
    )
    (net (code "97") (name "unconnected-(U11-PG-Pad4)") (class "Default")
      (node (ref "U11") (pin "4") (pinfunction "PG_4") (pintype "open_collector"))
    )
  )
)
